# SSB_Transceiver_SA612_Mixer.net
KiCad netlist of a schematic drawn in EAGLE
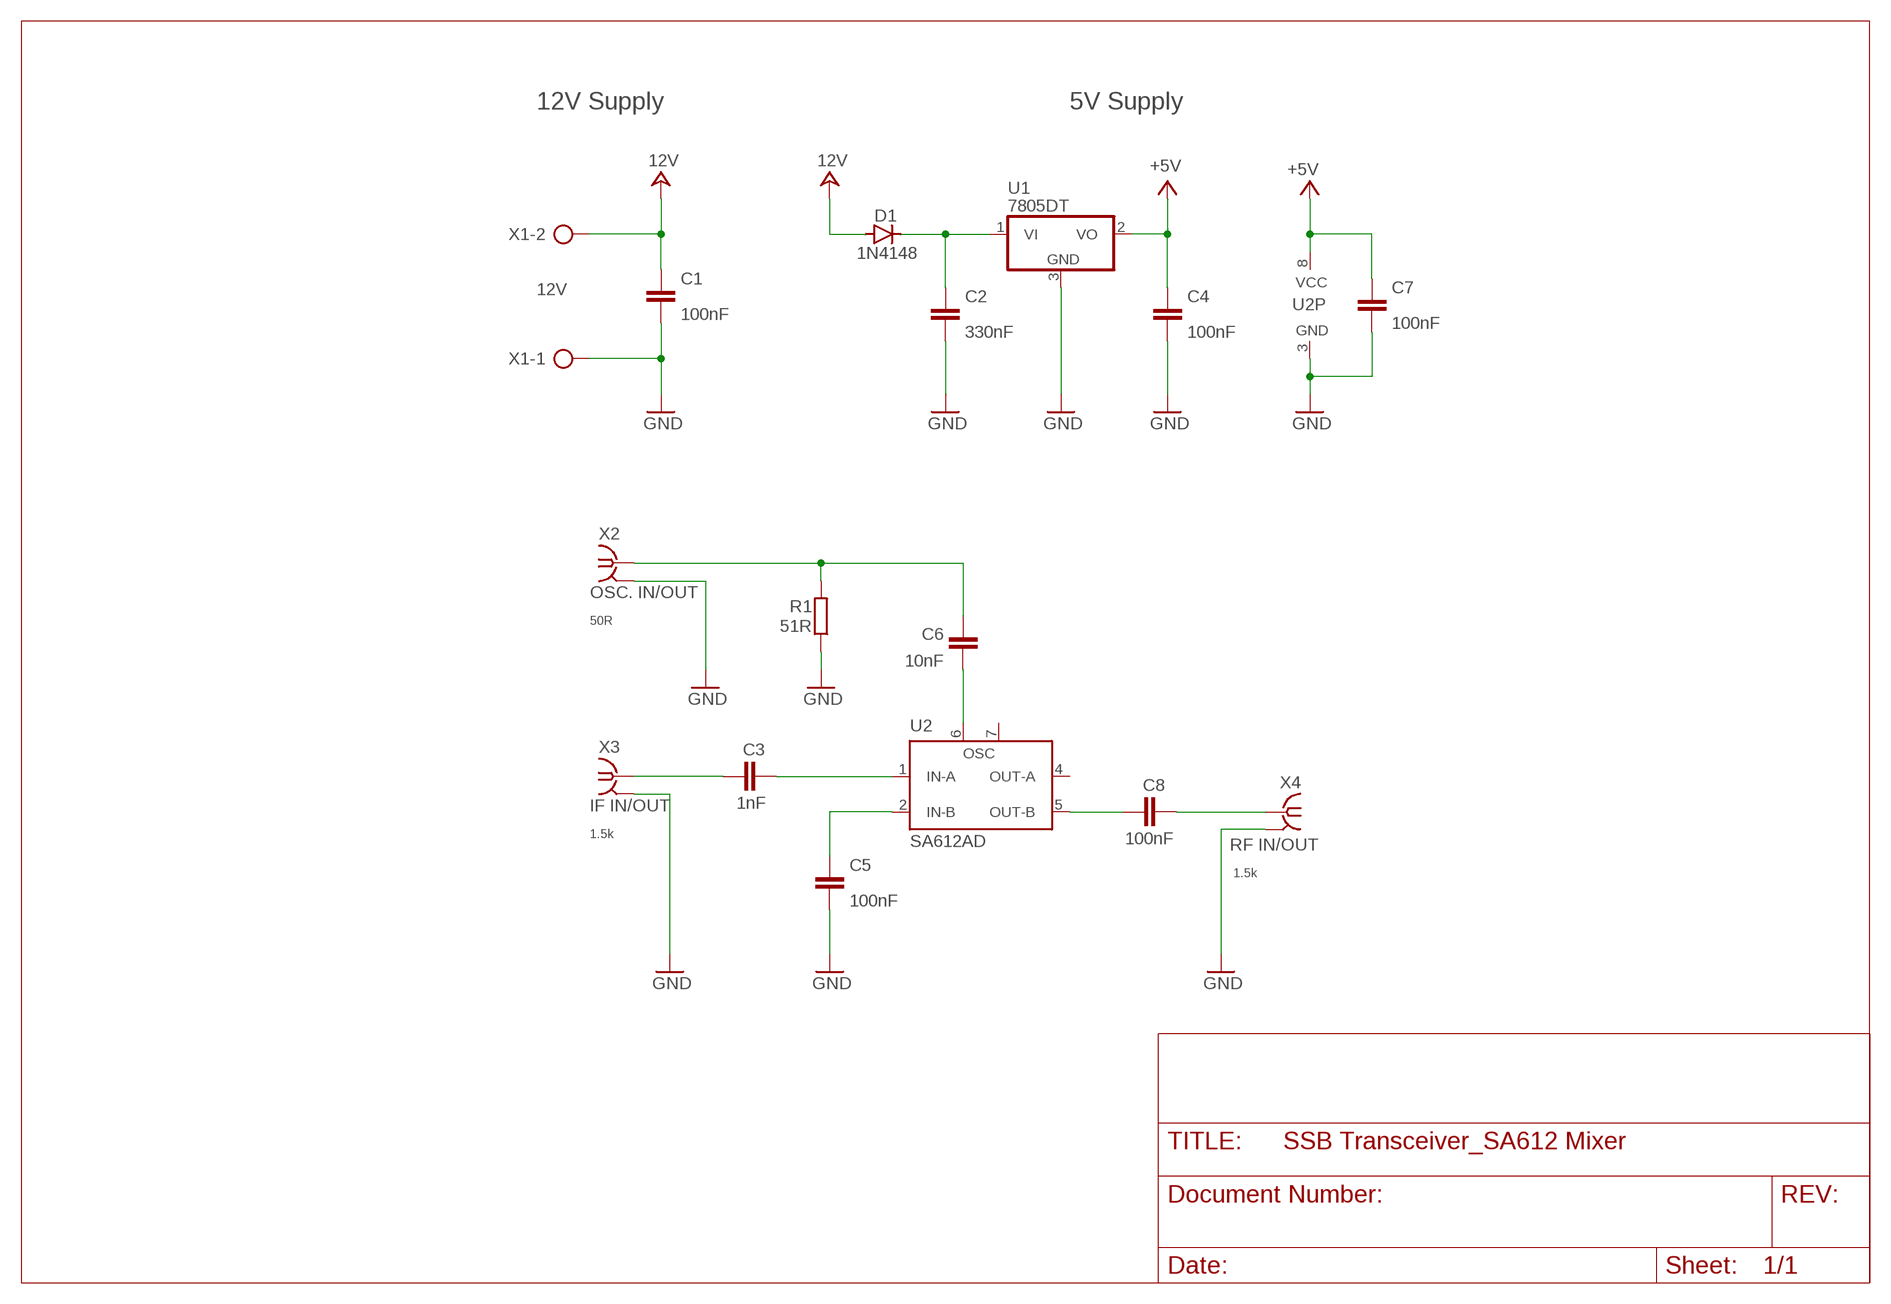
[diagram p0: schematic, sheet 1]

(export (version "E")
  (design (tool "Eeschema 10.0.6"))
  (components
    (comp (ref "C1")
      (value "100nF")
      (footprint "eagle-import:C0805")
      (libsource (lib "eagle-import") (part "C-EUC0805"))
    )
    (comp (ref "C2")
      (value "330nF")
      (footprint "eagle-import:C0805")
      (libsource (lib "eagle-import") (part "C-EUC0805"))
    )
    (comp (ref "C3")
      (value "1nF")
      (footprint "eagle-import:C0805")
      (libsource (lib "eagle-import") (part "C-EUC0805"))
    )
    (comp (ref "C4")
      (value "100nF")
      (footprint "eagle-import:C0805")
      (libsource (lib "eagle-import") (part "C-EUC0805"))
    )
    (comp (ref "C5")
      (value "100nF")
      (footprint "eagle-import:C0805")
      (libsource (lib "eagle-import") (part "C-EUC0805"))
    )
    (comp (ref "C6")
      (value "10nF")
      (footprint "eagle-import:C0805")
      (libsource (lib "eagle-import") (part "C-EUC0805"))
    )
    (comp (ref "C7")
      (value "100nF")
      (footprint "eagle-import:C0805")
      (libsource (lib "eagle-import") (part "C-EUC0805"))
    )
    (comp (ref "C8")
      (value "100nF")
      (footprint "eagle-import:C0805")
      (libsource (lib "eagle-import") (part "C-EUC0805"))
    )
    (comp (ref "D1")
      (value "1N4148")
      (footprint "eagle-import:SOD323-W")
      (libsource (lib "eagle-import") (part "DIODE-SOD323-W"))
    )
    (comp (ref "R1")
      (value "51R")
      (footprint "eagle-import:M0805")
      (libsource (lib "eagle-import") (part "R-EU_M0805"))
    )
    (comp (ref "U1")
      (value "7805DT")
      (footprint "eagle-import:TO252")
      (libsource (lib "eagle-import") (part "78DT05"))
    )
    (comp (ref "U2")
      (value "SA612AD")
      (footprint "eagle-import:SO08")
      (libsource (lib "eagle-import") (part "SA612AD"))
    )
    (comp (ref "X1")
      (value "12V")
      (footprint "eagle-import:AK300_2")
      (libsource (lib "eagle-import") (part "AK300/2"))
    )
    (comp (ref "X2")
      (value "OSC. IN/OUT")
      (footprint "eagle-import:J502-ND-142-0711-821_826")
      (fields (field (name "MF") "JOHNSON COMPONENTS") (field (name "MPN") "142-0711-821"))
      (libsource (lib "eagle-import") (part "SMA-142-0711-821/826"))
    )
    (comp (ref "X3")
      (value "IF IN/OUT")
      (footprint "eagle-import:J502-ND-142-0711-821_826")
      (fields (field (name "MF") "JOHNSON COMPONENTS") (field (name "MPN") "142-0711-821"))
      (libsource (lib "eagle-import") (part "SMA-142-0711-821/826"))
    )
    (comp (ref "X4")
      (value "RF IN/OUT")
      (footprint "eagle-import:J502-ND-142-0711-821_826")
      (fields (field (name "MF") "JOHNSON COMPONENTS") (field (name "MPN") "142-0711-821"))
      (libsource (lib "eagle-import") (part "SMA-142-0711-821/826"))
    )
  )
  (nets
    (net (code "1") (name "+5V") (class "Default")
      (node (ref "C4") (pin "2") (pinfunction "2_2") (pintype "passive"))
      (node (ref "C7") (pin "2") (pinfunction "2_2") (pintype "passive"))
      (node (ref "U1") (pin "2") (pinfunction "VO_2") (pintype "passive"))
      (node (ref "U2") (pin "8") (pinfunction "VCC_8") (pintype "power_in"))
    )
    (net (code "2") (name "12V") (class "Default")
      (node (ref "C1") (pin "2") (pinfunction "2_2") (pintype "passive"))
      (node (ref "D1") (pin "A") (pinfunction "A_A") (pintype "passive"))
      (node (ref "X1") (pin "2") (pinfunction "KL_2") (pintype "passive"))
    )
    (net (code "3") (name "GND") (class "Default")
      (node (ref "C1") (pin "1") (pinfunction "1_1") (pintype "passive"))
      (node (ref "C2") (pin "1") (pinfunction "1_1") (pintype "passive"))
      (node (ref "C4") (pin "1") (pinfunction "1_1") (pintype "passive"))
      (node (ref "C5") (pin "1") (pinfunction "1_1") (pintype "passive"))
      (node (ref "C7") (pin "1") (pinfunction "1_1") (pintype "passive"))
      (node (ref "R1") (pin "1") (pinfunction "1_1") (pintype "passive"))
      (node (ref "U1") (pin "3") (pinfunction "GND_3") (pintype "passive"))
      (node (ref "U2") (pin "3") (pinfunction "GND_3") (pintype "power_in"))
      (node (ref "X1") (pin "1") (pinfunction "KL_1") (pintype "passive"))
      (node (ref "X2") (pin "G@1") (pinfunction "2_G@1") (pintype "passive"))
      (node (ref "X2") (pin "G@2") (pinfunction "2_G@2") (pintype "passive"))
      (node (ref "X2") (pin "G@3") (pinfunction "2_G@3") (pintype "passive"))
      (node (ref "X2") (pin "G@4") (pinfunction "2_G@4") (pintype "passive"))
      (node (ref "X3") (pin "G@1") (pinfunction "2_G@1") (pintype "passive"))
      (node (ref "X3") (pin "G@2") (pinfunction "2_G@2") (pintype "passive"))
      (node (ref "X3") (pin "G@3") (pinfunction "2_G@3") (pintype "passive"))
      (node (ref "X3") (pin "G@4") (pinfunction "2_G@4") (pintype "passive"))
      (node (ref "X4") (pin "G@1") (pinfunction "2_G@1") (pintype "passive"))
      (node (ref "X4") (pin "G@2") (pinfunction "2_G@2") (pintype "passive"))
      (node (ref "X4") (pin "G@3") (pinfunction "2_G@3") (pintype "passive"))
      (node (ref "X4") (pin "G@4") (pinfunction "2_G@4") (pintype "passive"))
    )
    (net (code "4") (name "Net-(C3-Pad2)") (class "Default")
      (node (ref "C3") (pin "2") (pinfunction "2_2") (pintype "passive"))
      (node (ref "X3") (pin "1") (pinfunction "1_1") (pintype "passive"))
    )
    (net (code "5") (name "Net-(C6-Pad2)") (class "Default")
      (node (ref "C6") (pin "2") (pinfunction "2_2") (pintype "passive"))
      (node (ref "R1") (pin "2") (pinfunction "2_2") (pintype "passive"))
      (node (ref "X2") (pin "1") (pinfunction "1_1") (pintype "passive"))
    )
    (net (code "6") (name "Net-(C8-Pad1)") (class "Default")
      (node (ref "C8") (pin "1") (pinfunction "1_1") (pintype "passive"))
      (node (ref "X4") (pin "1") (pinfunction "1_1") (pintype "passive"))
    )
    (net (code "7") (name "Net-(U1-VI)") (class "Default")
      (node (ref "C2") (pin "2") (pinfunction "2_2") (pintype "passive"))
      (node (ref "D1") (pin "C") (pinfunction "C_C") (pintype "passive"))
      (node (ref "U1") (pin "1") (pinfunction "VI_1") (pintype "input"))
    )
    (net (code "8") (name "Net-(U2A-IN-A)") (class "Default")
      (node (ref "C3") (pin "1") (pinfunction "1_1") (pintype "passive"))
      (node (ref "U2") (pin "1") (pinfunction "IN-A_1") (pintype "input"))
    )
    (net (code "9") (name "Net-(U2A-IN-B)") (class "Default")
      (node (ref "C5") (pin "2") (pinfunction "2_2") (pintype "passive"))
      (node (ref "U2") (pin "2") (pinfunction "IN-B_2") (pintype "input"))
    )
    (net (code "10") (name "Net-(U2A-OSC)") (class "Default")
      (node (ref "C6") (pin "1") (pinfunction "1_1") (pintype "passive"))
      (node (ref "U2") (pin "6") (pinfunction "OSC_6") (pintype "passive"))
    )
    (net (code "11") (name "Net-(U2A-OUT-B)") (class "Default")
      (node (ref "C8") (pin "2") (pinfunction "2_2") (pintype "passive"))
      (node (ref "U2") (pin "5") (pinfunction "OUT-B_5") (pintype "input"))
    )
    (net (code "12") (name "unconnected-(U2A-OSC'-Pad7)") (class "Default")
      (node (ref "U2") (pin "7") (pinfunction "OSC'_7") (pintype "passive"))
    )
    (net (code "13") (name "unconnected-(U2A-OUT-A-Pad4)") (class "Default")
      (node (ref "U2") (pin "4") (pinfunction "OUT-A_4") (pintype "input"))
    )
  )
)
